# 2021-03-01_HALO_RGB_Board.net
KiCad netlist of a schematic drawn in EAGLE
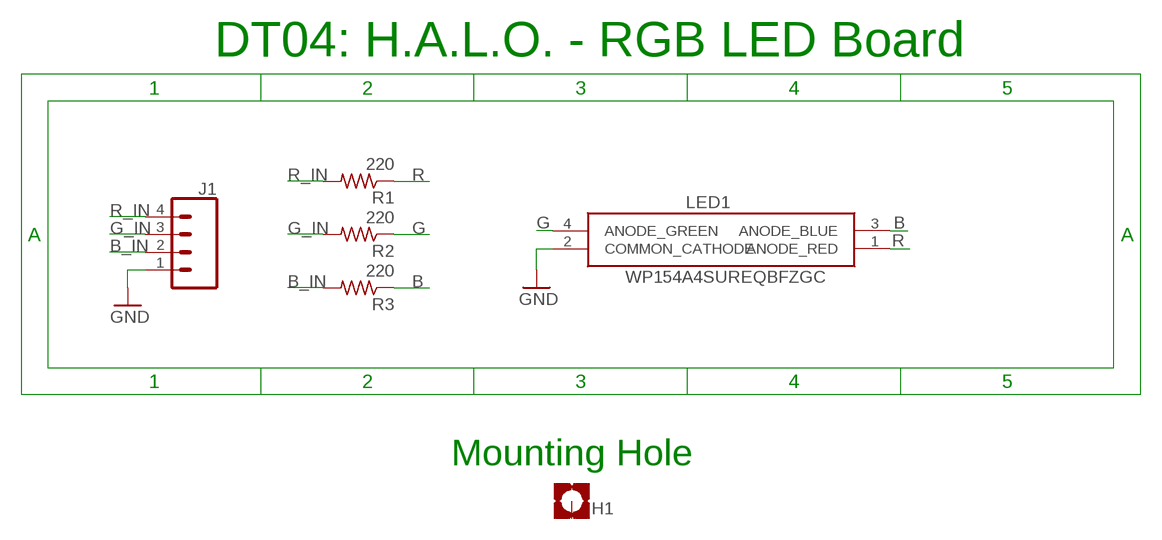
[diagram p0: schematic, sheet 1]

(export (version "E")
  (design (tool "Eeschema 10.0.6"))
  (components
    (comp (ref "H1")
      (value "MOUNT-PAD-SQUARE3.0")
      (footprint "eagle-import:3,0-PAD-SQUARE")
      (libsource (lib "eagle-import") (part "MOUNT-PAD-SQUARE3.0"))
    )
    (comp (ref "J1")
      (value "CONN_04")
      (footprint "eagle-import:1X04")
      (libsource (lib "eagle-import") (part "CONN_04"))
    )
    (comp (ref "LED1")
      (value "WP154A4SUREQBFZGC")
      (footprint "eagle-import:L-154A4SUREQBFZGEC")
      (fields (field (name "MOUSER_PART_NUMBER") "604-WP154A4SUREQBFZG"))
      (libsource (lib "eagle-import") (part "WP154A4SUREQBFZGC"))
    )
    (comp (ref "R1")
      (value "220")
      (footprint "eagle-import:R0805")
      (libsource (lib "eagle-import") (part "R-US_R0805"))
    )
    (comp (ref "R2")
      (value "220")
      (footprint "eagle-import:R0805")
      (libsource (lib "eagle-import") (part "R-US_R0805"))
    )
    (comp (ref "R3")
      (value "220")
      (footprint "eagle-import:R0805")
      (libsource (lib "eagle-import") (part "R-US_R0805"))
    )
  )
  (nets
    (net (code "1") (name "/B") (class "Default")
      (node (ref "LED1") (pin "3") (pinfunction "ANODE_BLUE_3") (pintype "bidirectional"))
      (node (ref "R3") (pin "1") (pinfunction "1_1") (pintype "passive"))
    )
    (net (code "2") (name "/B_IN") (class "Default")
      (node (ref "J1") (pin "2") (pinfunction "2_2") (pintype "passive"))
      (node (ref "R3") (pin "2") (pinfunction "2_2") (pintype "passive"))
    )
    (net (code "3") (name "/G") (class "Default")
      (node (ref "LED1") (pin "4") (pinfunction "ANODE_GREEN_4") (pintype "bidirectional"))
      (node (ref "R2") (pin "1") (pinfunction "1_1") (pintype "passive"))
    )
    (net (code "4") (name "/G_IN") (class "Default")
      (node (ref "J1") (pin "3") (pinfunction "3_3") (pintype "passive"))
      (node (ref "R2") (pin "2") (pinfunction "2_2") (pintype "passive"))
    )
    (net (code "5") (name "/R") (class "Default")
      (node (ref "LED1") (pin "1") (pinfunction "ANODE_RED_1") (pintype "bidirectional"))
      (node (ref "R1") (pin "1") (pinfunction "1_1") (pintype "passive"))
    )
    (net (code "6") (name "/R_IN") (class "Default")
      (node (ref "J1") (pin "4") (pinfunction "4_4") (pintype "passive"))
      (node (ref "R1") (pin "2") (pinfunction "2_2") (pintype "passive"))
    )
    (net (code "7") (name "GND") (class "Default")
      (node (ref "J1") (pin "1") (pinfunction "1_1") (pintype "passive"))
      (node (ref "LED1") (pin "2") (pinfunction "COMMON_CATHODE_2") (pintype "bidirectional"))
    )
    (net (code "8") (name "unconnected-(H1-MOUNT-PadB3,0)") (class "Default")
      (node (ref "H1") (pin "B3,0") (pinfunction "MOUNT_B3,0") (pintype "passive"))
    )
  )
)
